# 06_SENSOR.net
KiCad netlist of a schematic drawn in Altium Designer
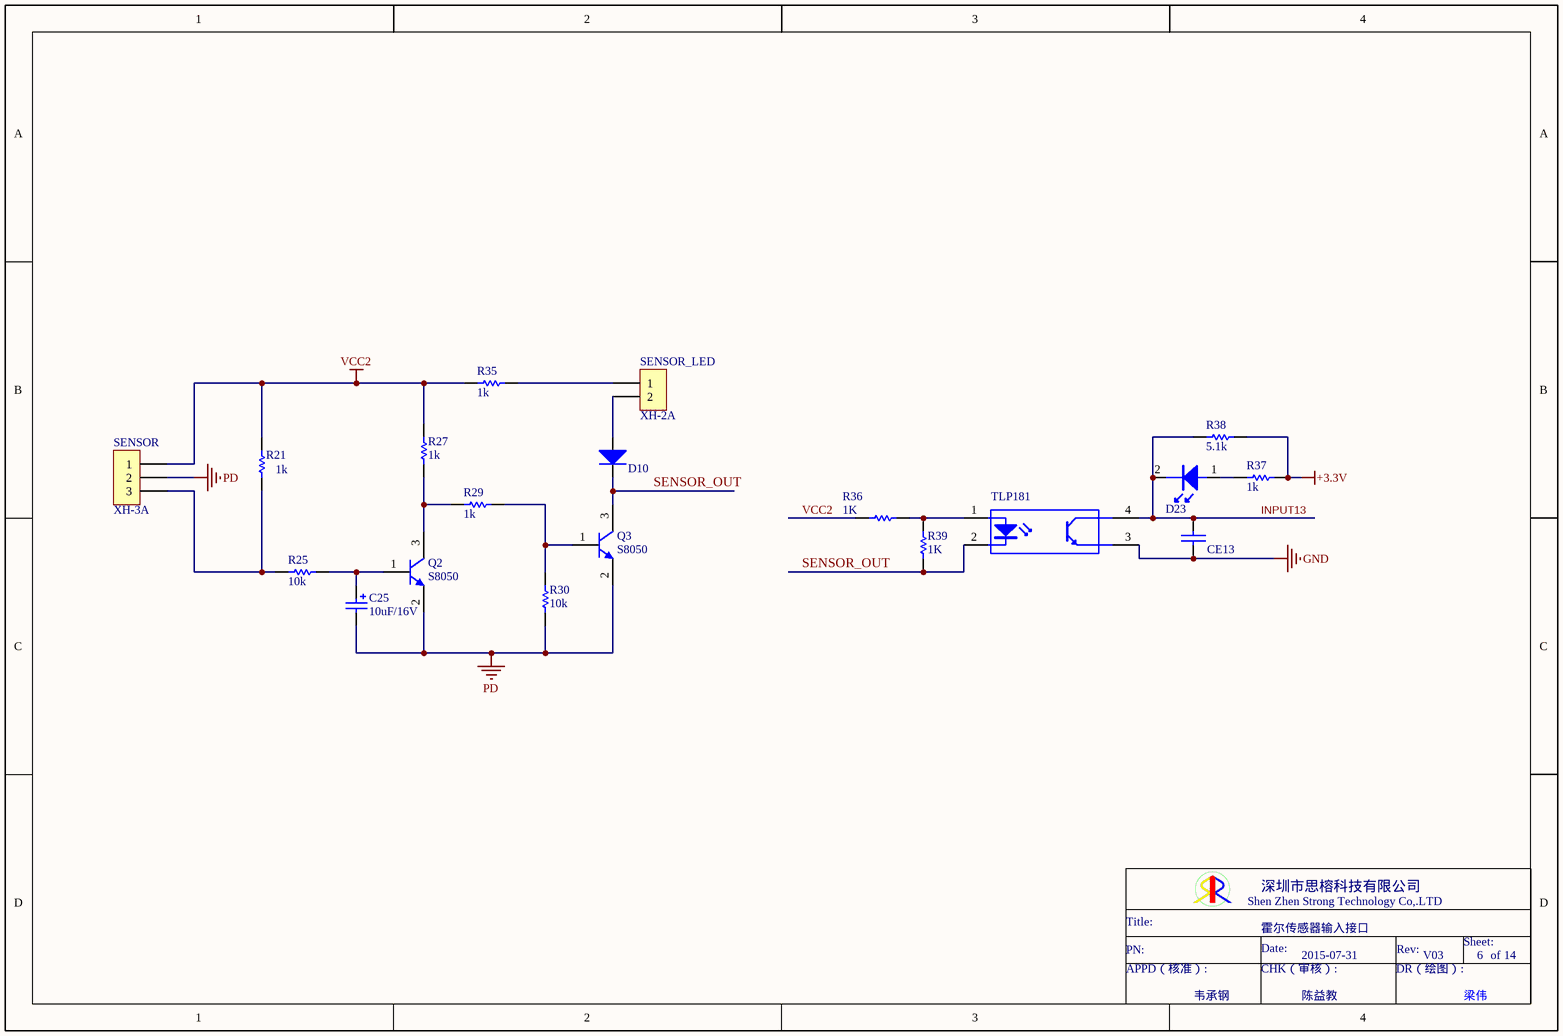
[diagram p0: 06_SENSOR.SchDoc]

(export (version "E")
  (design (tool "Eeschema 10.0.6"))
  (components
    (comp (ref "C25")
      (value "10uF/16V")
      (footprint "A")
      (description "Polarized Capacitor (Axial)")
      (fields (field (name "PUBLISHER") "Altium Limited"))
      (libsource (lib "Miscellaneous Devices") (part "Cap Pol2"))
    )
    (comp (ref "CE13")
      (value "100pF")
      (footprint "0603C")
      (description "Capacitor")
      (libsource (lib "Mylibrary") (part "CAP"))
    )
    (comp (ref "D10")
      (value "IN4148W T4")
      (footprint "1206D")
      (description "二极管")
      (libsource (lib "Mylibrary") (part "D"))
    )
    (comp (ref "D23")
      (value "LED灯 白发红光")
      (footprint "D0603")
      (description "LED灯")
      (libsource (lib "Mylibrary") (part "LED"))
    )
    (comp (ref "Q2")
      (value "S8050")
      (footprint "SOT23")
      (description "NPN Bipolar Transistor")
      (fields (field (name "PUBLISHER") "Altium Limited"))
      (libsource (lib "Miscellaneous Devices") (part "QNPN"))
    )
    (comp (ref "Q3")
      (value "S8050")
      (footprint "SOT23")
      (description "NPN Bipolar Transistor")
      (fields (field (name "PUBLISHER") "Altium Limited"))
      (libsource (lib "Miscellaneous Devices") (part "QNPN"))
    )
    (comp (ref "R21") (value "1k") (footprint "0603R") (libsource (lib "Mylibrary") (part "RES")))
    (comp (ref "R25") (value "10k") (footprint "0603R") (libsource (lib "Mylibrary") (part "RES")))
    (comp (ref "R27") (value "1k") (footprint "0603R") (libsource (lib "Mylibrary") (part "RES")))
    (comp (ref "R29") (value "1k") (footprint "0603R") (libsource (lib "Mylibrary") (part "RES")))
    (comp (ref "R30") (value "10k") (footprint "0603R") (libsource (lib "Mylibrary") (part "RES")))
    (comp (ref "R35") (value "1k") (footprint "0603R") (libsource (lib "Mylibrary") (part "RES")))
    (comp (ref "R36") (value "1K") (footprint "0805R") (libsource (lib "Mylibrary") (part "RES")))
    (comp (ref "R37") (value "1k") (footprint "0603R") (libsource (lib "Mylibrary") (part "RES")))
    (comp (ref "R38") (value "5.1k") (footprint "0603R") (libsource (lib "Mylibrary") (part "RES")))
    (comp (ref "R39") (value "1K") (footprint "0603R") (libsource (lib "Mylibrary") (part "RES")))
    (comp (ref "SENSOR") (value "XH-3A") (footprint "CN3-2.54") (libsource (lib "Mylibrary") (part "CON3")))
    (comp (ref "SENSOR_LED")
      (value "XH-2A")
      (footprint "CN2-2.54")
      (libsource (lib "WeiCHGSCH") (part "CON2"))
    )
    (comp (ref "U16") (value "TLP181") (footprint "SOP4-2.54") (libsource (lib "WeiCHGSCH") (part "TLP521")))
  )
  (nets
    (net (code "1") (name "+3.3V") (class "Default")
      (node (ref "R37") (pin "1") (pinfunction "1_1") (pintype "passive"))
      (node (ref "R38") (pin "1") (pinfunction "1_1") (pintype "passive"))
    )
    (net (code "2") (name "/INPUT13") (class "Default")
      (node (ref "CE13") (pin "1") (pinfunction "1_1") (pintype "passive"))
      (node (ref "D23") (pin "2") (pinfunction "2_2") (pintype "passive"))
      (node (ref "R38") (pin "2") (pinfunction "2_2") (pintype "passive"))
      (node (ref "U16") (pin "4") (pinfunction "C_4") (pintype "passive"))
    )
    (net (code "3") (name "/SENSOR_OUT") (class "Default")
      (node (ref "D10") (pin "2") (pinfunction "2_2") (pintype "passive"))
      (node (ref "Q3") (pin "3") (pinfunction "C_3") (pintype "passive"))
      (node (ref "R39") (pin "2") (pinfunction "2_2") (pintype "passive"))
      (node (ref "U16") (pin "2") (pinfunction "K_2") (pintype "passive"))
    )
    (net (code "4") (name "GND") (class "Default")
      (node (ref "CE13") (pin "2") (pinfunction "2_2") (pintype "passive"))
      (node (ref "U16") (pin "3") (pinfunction "E_3") (pintype "passive"))
    )
    (net (code "5") (name "Net-(D10-Pad1)") (class "Default")
      (node (ref "D10") (pin "1") (pinfunction "1_1") (pintype "passive"))
      (node (ref "SENSOR_LED") (pin "2") (pinfunction "2_2") (pintype "passive"))
    )
    (net (code "6") (name "Net-(D23-Pad1)") (class "Default")
      (node (ref "D23") (pin "1") (pinfunction "1_1") (pintype "passive"))
      (node (ref "R37") (pin "2") (pinfunction "2_2") (pintype "passive"))
    )
    (net (code "7") (name "Net-(Q2-B)") (class "Default")
      (node (ref "C25") (pin "1") (pinfunction "1_1") (pintype "passive"))
      (node (ref "Q2") (pin "1") (pinfunction "B_1") (pintype "passive"))
      (node (ref "R25") (pin "1") (pinfunction "1_1") (pintype "passive"))
    )
    (net (code "8") (name "Net-(Q2-C)") (class "Default")
      (node (ref "Q2") (pin "3") (pinfunction "C_3") (pintype "passive"))
      (node (ref "R27") (pin "1") (pinfunction "1_1") (pintype "passive"))
      (node (ref "R29") (pin "2") (pinfunction "2_2") (pintype "passive"))
    )
    (net (code "9") (name "Net-(Q3-B)") (class "Default")
      (node (ref "Q3") (pin "1") (pinfunction "B_1") (pintype "passive"))
      (node (ref "R29") (pin "1") (pinfunction "1_1") (pintype "passive"))
      (node (ref "R30") (pin "2") (pinfunction "2_2") (pintype "passive"))
    )
    (net (code "10") (name "Net-(R21-Pad2)") (class "Default")
      (node (ref "R21") (pin "2") (pinfunction "2_2") (pintype "passive"))
      (node (ref "R25") (pin "2") (pinfunction "2_2") (pintype "passive"))
      (node (ref "SENSOR") (pin "3") (pinfunction "3_3") (pintype "passive"))
    )
    (net (code "11") (name "Net-(R35-Pad2)") (class "Default")
      (node (ref "R35") (pin "2") (pinfunction "2_2") (pintype "passive"))
      (node (ref "SENSOR_LED") (pin "1") (pinfunction "1_1") (pintype "passive"))
    )
    (net (code "12") (name "Net-(U16-A)") (class "Default")
      (node (ref "R36") (pin "1") (pinfunction "1_1") (pintype "passive"))
      (node (ref "R39") (pin "1") (pinfunction "1_1") (pintype "passive"))
      (node (ref "U16") (pin "1") (pinfunction "A_1") (pintype "passive"))
    )
    (net (code "13") (name "PD") (class "Default")
      (node (ref "C25") (pin "2") (pinfunction "2_2") (pintype "passive"))
      (node (ref "Q2") (pin "2") (pinfunction "E_2") (pintype "passive"))
      (node (ref "Q3") (pin "2") (pinfunction "E_2") (pintype "passive"))
      (node (ref "R30") (pin "1") (pinfunction "1_1") (pintype "passive"))
      (node (ref "SENSOR") (pin "2") (pinfunction "2_2") (pintype "passive"))
    )
    (net (code "14") (name "VCC2") (class "Default")
      (node (ref "R21") (pin "1") (pinfunction "1_1") (pintype "passive"))
      (node (ref "R27") (pin "2") (pinfunction "2_2") (pintype "passive"))
      (node (ref "R35") (pin "1") (pinfunction "1_1") (pintype "passive"))
      (node (ref "R36") (pin "2") (pinfunction "2_2") (pintype "passive"))
      (node (ref "SENSOR") (pin "1") (pinfunction "1_1") (pintype "passive"))
    )
  )
)
